# Main.net
KiCad netlist of a schematic drawn in Altium Designer
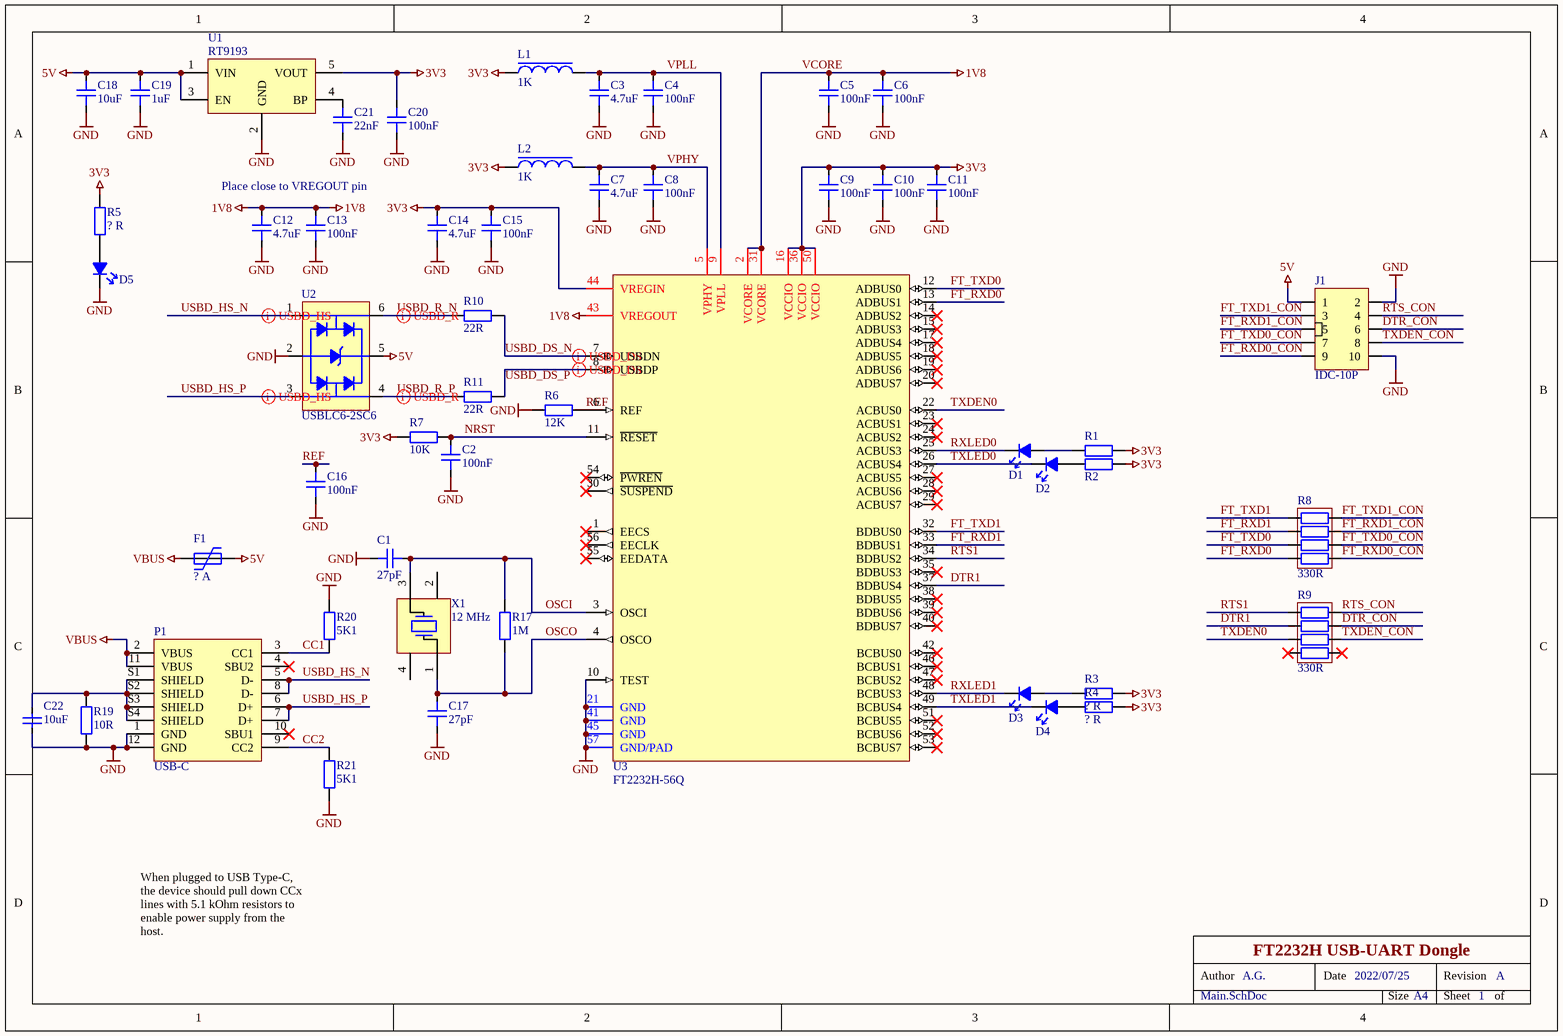
[diagram p0: Main.SchDoc]

(export (version "E")
  (design (tool "Eeschema 10.0.6"))
  (components
    (comp (ref "C1")
      (value "27pF")
      (footprint "0603C_RF_M")
      (description "Capacitor")
      (fields (field (name "TOLERANCE") "?") (field (name "MANUFACTURER") "Generic Brand"))
      (libsource (lib "AG.Generic") (part "C"))
    )
    (comp (ref "C2")
      (value "100nF")
      (footprint "0603C_RF_M")
      (description "Capacitor")
      (fields (field (name "TOLERANCE") "?") (field (name "MANUFACTURER") "Generic Brand"))
      (libsource (lib "AG.Generic") (part "C"))
    )
    (comp (ref "C3")
      (value "4.7uF")
      (footprint "0603C_RF_M")
      (description "Capacitor")
      (fields (field (name "TOLERANCE") "?") (field (name "MANUFACTURER") "Generic Brand"))
      (libsource (lib "AG.Generic") (part "C"))
    )
    (comp (ref "C4")
      (value "100nF")
      (footprint "0603C_RF_M")
      (description "Capacitor")
      (fields (field (name "TOLERANCE") "?") (field (name "MANUFACTURER") "Generic Brand"))
      (libsource (lib "AG.Generic") (part "C"))
    )
    (comp (ref "C5")
      (value "100nF")
      (footprint "0603C_RF_M")
      (description "Capacitor")
      (fields (field (name "TOLERANCE") "?") (field (name "MANUFACTURER") "Generic Brand"))
      (libsource (lib "AG.Generic") (part "C"))
    )
    (comp (ref "C6")
      (value "100nF")
      (footprint "0603C_RF_M")
      (description "Capacitor")
      (fields (field (name "TOLERANCE") "?") (field (name "MANUFACTURER") "Generic Brand"))
      (libsource (lib "AG.Generic") (part "C"))
    )
    (comp (ref "C7")
      (value "4.7uF")
      (footprint "0603C_RF_M")
      (description "Capacitor")
      (fields (field (name "TOLERANCE") "?") (field (name "MANUFACTURER") "Generic Brand"))
      (libsource (lib "AG.Generic") (part "C"))
    )
    (comp (ref "C8")
      (value "100nF")
      (footprint "0603C_RF_M")
      (description "Capacitor")
      (fields (field (name "TOLERANCE") "?") (field (name "MANUFACTURER") "Generic Brand"))
      (libsource (lib "AG.Generic") (part "C"))
    )
    (comp (ref "C9")
      (value "100nF")
      (footprint "0603C_RF_M")
      (description "Capacitor")
      (fields (field (name "TOLERANCE") "?") (field (name "MANUFACTURER") "Generic Brand"))
      (libsource (lib "AG.Generic") (part "C"))
    )
    (comp (ref "C10")
      (value "100nF")
      (footprint "0603C_RF_M")
      (description "Capacitor")
      (fields (field (name "TOLERANCE") "?") (field (name "MANUFACTURER") "Generic Brand"))
      (libsource (lib "AG.Generic") (part "C"))
    )
    (comp (ref "C11")
      (value "100nF")
      (footprint "0603C_RF_M")
      (description "Capacitor")
      (fields (field (name "TOLERANCE") "?") (field (name "MANUFACTURER") "Generic Brand"))
      (libsource (lib "AG.Generic") (part "C"))
    )
    (comp (ref "C12")
      (value "4.7uF")
      (footprint "0603C_RF_M")
      (description "Capacitor")
      (fields (field (name "TOLERANCE") "?") (field (name "MANUFACTURER") "Generic Brand"))
      (libsource (lib "AG.Generic") (part "C"))
    )
    (comp (ref "C13")
      (value "100nF")
      (footprint "0603C_RF_M")
      (description "Capacitor")
      (fields (field (name "TOLERANCE") "?") (field (name "MANUFACTURER") "Generic Brand"))
      (libsource (lib "AG.Generic") (part "C"))
    )
    (comp (ref "C14")
      (value "4.7uF")
      (footprint "0603C_RF_M")
      (description "Capacitor")
      (fields (field (name "TOLERANCE") "?") (field (name "MANUFACTURER") "Generic Brand"))
      (libsource (lib "AG.Generic") (part "C"))
    )
    (comp (ref "C15")
      (value "100nF")
      (footprint "0603C_RF_M")
      (description "Capacitor")
      (fields (field (name "TOLERANCE") "?") (field (name "MANUFACTURER") "Generic Brand"))
      (libsource (lib "AG.Generic") (part "C"))
    )
    (comp (ref "C16")
      (value "100nF")
      (footprint "0603C_RF_M")
      (description "Capacitor")
      (fields (field (name "TOLERANCE") "?") (field (name "MANUFACTURER") "Generic Brand"))
      (libsource (lib "AG.Generic") (part "C"))
    )
    (comp (ref "C17")
      (value "27pF")
      (footprint "0603C_RF_M")
      (description "Capacitor")
      (fields (field (name "TOLERANCE") "?") (field (name "MANUFACTURER") "Generic Brand"))
      (libsource (lib "AG.Generic") (part "C"))
    )
    (comp (ref "C18")
      (value "10uF")
      (footprint "0603C_RF_M")
      (description "Capacitor")
      (fields (field (name "TOLERANCE") "?") (field (name "MANUFACTURER") "Generic Brand"))
      (libsource (lib "AG.Generic") (part "C"))
    )
    (comp (ref "C19")
      (value "1uF")
      (footprint "0603C_RF_M")
      (description "Capacitor")
      (fields (field (name "TOLERANCE") "?") (field (name "MANUFACTURER") "Generic Brand"))
      (libsource (lib "AG.Generic") (part "C"))
    )
    (comp (ref "C20")
      (value "100nF")
      (footprint "0603C_RF_M")
      (description "Capacitor")
      (fields (field (name "TOLERANCE") "?") (field (name "MANUFACTURER") "Generic Brand"))
      (libsource (lib "AG.Generic") (part "C"))
    )
    (comp (ref "C21")
      (value "22nF")
      (footprint "0603C_RF_M")
      (description "Capacitor")
      (fields (field (name "TOLERANCE") "?") (field (name "MANUFACTURER") "Generic Brand"))
      (libsource (lib "AG.Generic") (part "C"))
    )
    (comp (ref "C22")
      (value "10uF")
      (footprint "0603C_RF_M")
      (description "Capacitor")
      (fields (field (name "TOLERANCE") "?") (field (name "MANUFACTURER") "Generic Brand"))
      (libsource (lib "") (part "C_1"))
    )
    (comp (ref "D1")
      (value "Unspecified")
      (footprint "0805LED_RF_M")
      (description "LED")
      (fields (field (name "MANUFACTURER") "Generic Brand"))
      (libsource (lib "AG.Generic") (part "LED"))
    )
    (comp (ref "D2")
      (value "Unspecified")
      (footprint "0805LED_RF_M")
      (description "LED")
      (fields (field (name "MANUFACTURER") "Generic Brand"))
      (libsource (lib "AG.Generic") (part "LED"))
    )
    (comp (ref "D3")
      (value "Unspecified")
      (footprint "0805LED_RF_M")
      (description "LED")
      (fields (field (name "MANUFACTURER") "Generic Brand"))
      (libsource (lib "AG.Generic") (part "LED"))
    )
    (comp (ref "D4")
      (value "Unspecified")
      (footprint "0805LED_RF_M")
      (description "LED")
      (fields (field (name "MANUFACTURER") "Generic Brand"))
      (libsource (lib "AG.Generic") (part "LED"))
    )
    (comp (ref "D5")
      (value "Unspecified")
      (footprint "0805LED_RF_M")
      (description "LED")
      (fields (field (name "MANUFACTURER") "Generic Brand"))
      (libsource (lib "AG.Generic") (part "LED"))
    )
    (comp (ref "F1")
      (value "? A")
      (footprint "AG.Passive:PTC_0805_RF_M")
      (description "Resettable Fuse")
      (fields (field (name "MANUFACTURER") "Generic Brand"))
      (libsource (lib "AG.Generic") (part "PPTC"))
    )
    (comp (ref "J1")
      (value "IDC-10P")
      (footprint "AG.Connectors:IDC-10_100MIL_SIDE")
      (description "IDC Connector Header Double Row 10 Position")
      (fields
        (field (name "MANUFACTURER") "Wurth Elektronik")
        (field (name "MANUFACTURER PART NO") "61201021621")
      )
      (libsource (lib "AG.Connectors") (part "IDC-10P"))
    )
    (comp (ref "L1")
      (value "1K")
      (footprint "AG.Chip:0603C_RF_M")
      (description "Ferrite Bead")
      (libsource (lib "AG.Generic") (part "FB"))
    )
    (comp (ref "L2")
      (value "1K")
      (footprint "AG.Chip:0603C_RF_M")
      (description "Ferrite Bead")
      (libsource (lib "AG.Generic") (part "FB"))
    )
    (comp (ref "P1")
      (value "USB-C")
      (footprint "AG.Connectors:USBC-16P-TH")
      (description "USB Type C Socket 16-Pin")
      (libsource (lib "AG.Connectors") (part "USBC-16P-TH"))
    )
    (comp (ref "R1")
      (value "? R")
      (footprint "0603R_RF_M")
      (description "Resistor")
      (fields (field (name "TOLERANCE") "?") (field (name "MANUFACTURER") "Generic Brand"))
      (libsource (lib "AG.Generic") (part "R"))
    )
    (comp (ref "R2")
      (value "? R")
      (footprint "0603R_RF_M")
      (description "Resistor")
      (fields (field (name "TOLERANCE") "?") (field (name "MANUFACTURER") "Generic Brand"))
      (libsource (lib "AG.Generic") (part "R"))
    )
    (comp (ref "R3")
      (value "? R")
      (footprint "0603R_RF_M")
      (description "Resistor")
      (fields (field (name "TOLERANCE") "?") (field (name "MANUFACTURER") "Generic Brand"))
      (libsource (lib "AG.Generic") (part "R"))
    )
    (comp (ref "R4")
      (value "? R")
      (footprint "0603R_RF_M")
      (description "Resistor")
      (fields (field (name "TOLERANCE") "?") (field (name "MANUFACTURER") "Generic Brand"))
      (libsource (lib "AG.Generic") (part "R"))
    )
    (comp (ref "R5")
      (value "? R")
      (footprint "0603R_RF_M")
      (description "Resistor")
      (fields (field (name "TOLERANCE") "?") (field (name "MANUFACTURER") "Generic Brand"))
      (libsource (lib "AG.Generic") (part "R"))
    )
    (comp (ref "R6")
      (value "12K")
      (footprint "0603R_RF_M")
      (description "Resistor")
      (fields (field (name "TOLERANCE") "?") (field (name "MANUFACTURER") "Generic Brand"))
      (libsource (lib "AG.Generic") (part "R"))
    )
    (comp (ref "R7")
      (value "10K")
      (footprint "0603R_RF_M")
      (description "Resistor")
      (fields (field (name "TOLERANCE") "?") (field (name "MANUFACTURER") "Generic Brand"))
      (libsource (lib "AG.Generic") (part "R"))
    )
    (comp (ref "R8")
      (value "330R")
      (footprint "Chip:R0603_ARR_4R_CNVX_RF_H")
      (description "Resistor Array 4x Isolated")
      (libsource (lib "AG.Generic") (part "RA-4"))
    )
    (comp (ref "R9")
      (value "330R")
      (footprint "Chip:R0603_ARR_4R_CNVX_RF_H")
      (description "Resistor Array 4x Isolated")
      (libsource (lib "AG.Generic") (part "RA-4"))
    )
    (comp (ref "R10")
      (value "22R")
      (footprint "Chip:R0402_RF_M")
      (description "Resistor")
      (fields (field (name "TOLERANCE") "?") (field (name "MANUFACTURER") "Generic Brand"))
      (libsource (lib "AG.Generic") (part "R"))
    )
    (comp (ref "R11")
      (value "22R")
      (footprint "Chip:R0402_RF_M")
      (description "Resistor")
      (fields (field (name "TOLERANCE") "?") (field (name "MANUFACTURER") "Generic Brand"))
      (libsource (lib "AG.Generic") (part "R"))
    )
    (comp (ref "R17")
      (value "1M")
      (footprint "0603R_RF_M")
      (description "Resistor")
      (fields (field (name "TOLERANCE") "?") (field (name "MANUFACTURER") "Generic Brand"))
      (libsource (lib "AG.Generic") (part "R"))
    )
    (comp (ref "R19")
      (value "10R")
      (footprint "0603R_RF_M")
      (description "Resistor")
      (fields (field (name "TOLERANCE") "?") (field (name "MANUFACTURER") "Generic Brand"))
      (libsource (lib "AG.Generic") (part "R"))
    )
    (comp (ref "R20")
      (value "5K1")
      (footprint "0603R_RF_M")
      (description "Resistor")
      (fields (field (name "TOLERANCE") "?") (field (name "MANUFACTURER") "Generic Brand"))
      (libsource (lib "AG.Generic") (part "R"))
    )
    (comp (ref "R21")
      (value "5K1")
      (footprint "0603R_RF_M")
      (description "Resistor")
      (fields (field (name "TOLERANCE") "?") (field (name "MANUFACTURER") "Generic Brand"))
      (libsource (lib "AG.Generic") (part "R"))
    )
    (comp (ref "U1")
      (value "RT9193")
      (footprint "AG.IC:TI_SOT-23-5")
      (description "IC REG LINEAR 300MA SOT23-5")
      (libsource (lib "AG.IC") (part "RT9193"))
    )
    (comp (ref "U2")
      (value "USBLC6-2SC6")
      (footprint "TI_SOT-23-6")
      (description "Low Capacitance USB ESD Protection")
      (fields (field (name "MANUFACTURER") "STMicroelectronics"))
      (libsource (lib "AG.Discrete") (part "USBLC6-2SC6"))
    )
    (comp (ref "U3")
      (value "FT2232H-56Q")
      (footprint "FTDI_VQFN-56_RF_M")
      (description "IC DUAL USB TO UART/FIFO 56VQFN")
      (fields (field (name "MANUFACTURER") "Future Technology Devices International Ltd"))
      (libsource (lib "AG.IC") (part "FT2232H-56Q"))
    )
    (comp (ref "X1")
      (value "12 MHz")
      (footprint "XTAL_3225")
      (description "Crystal Resonator (4 Leads)")
      (fields (field (name "MANUFACTURER") "Generic Brand") (field (name "TOLERANCE") "? ppm"))
      (libsource (lib "AG.Generic") (part "XT-4P"))
    )
  )
  (nets
    (net (code "1") (name "/CC1") (class "Default")
      (node (ref "P1") (pin "3") (pinfunction "CC1_3") (pintype "passive"))
      (node (ref "R20") (pin "2") (pintype "passive"))
    )
    (net (code "2") (name "/CC2") (class "Default")
      (node (ref "P1") (pin "9") (pinfunction "CC2_9") (pintype "passive"))
      (node (ref "R21") (pin "1") (pintype "passive"))
    )
    (net (code "3") (name "/DTR1") (class "Default")
      (node (ref "R9") (pin "2") (pintype "passive"))
      (node (ref "U3") (pin "37") (pinfunction "BDBUS4_37") (pintype "bidirectional"))
    )
    (net (code "4") (name "/DTR_CON") (class "Default")
      (node (ref "J1") (pin "6") (pinfunction "6_6") (pintype "passive"))
      (node (ref "R9") (pin "7") (pintype "passive"))
    )
    (net (code "5") (name "/FT_RXD0") (class "Default")
      (node (ref "R8") (pin "4") (pintype "passive"))
      (node (ref "U3") (pin "13") (pinfunction "ADBUS1_13") (pintype "bidirectional"))
    )
    (net (code "6") (name "/FT_RXD0_CON") (class "Default")
      (node (ref "J1") (pin "9") (pinfunction "9_9") (pintype "passive"))
      (node (ref "R8") (pin "5") (pintype "passive"))
    )
    (net (code "7") (name "/FT_RXD1") (class "Default")
      (node (ref "R8") (pin "2") (pintype "passive"))
      (node (ref "U3") (pin "33") (pinfunction "BDBUS1_33") (pintype "bidirectional"))
    )
    (net (code "8") (name "/FT_RXD1_CON") (class "Default")
      (node (ref "J1") (pin "5") (pinfunction "5_5") (pintype "passive"))
      (node (ref "R8") (pin "7") (pintype "passive"))
    )
    (net (code "9") (name "/FT_TXD0") (class "Default")
      (node (ref "R8") (pin "3") (pintype "passive"))
      (node (ref "U3") (pin "12") (pinfunction "ADBUS0_12") (pintype "bidirectional"))
    )
    (net (code "10") (name "/FT_TXD0_CON") (class "Default")
      (node (ref "J1") (pin "7") (pinfunction "7_7") (pintype "passive"))
      (node (ref "R8") (pin "6") (pintype "passive"))
    )
    (net (code "11") (name "/FT_TXD1") (class "Default")
      (node (ref "R8") (pin "1") (pintype "passive"))
      (node (ref "U3") (pin "32") (pinfunction "BDBUS0_32") (pintype "bidirectional"))
    )
    (net (code "12") (name "/FT_TXD1_CON") (class "Default")
      (node (ref "J1") (pin "3") (pinfunction "3_3") (pintype "passive"))
      (node (ref "R8") (pin "8") (pintype "passive"))
    )
    (net (code "13") (name "/NRST") (class "Default")
      (node (ref "C2") (pin "1") (pinfunction "1_1") (pintype "passive"))
      (node (ref "R7") (pin "2") (pintype "passive"))
      (node (ref "U3") (pin "11") (pinfunction "~{RESET}_11") (pintype "input"))
    )
    (net (code "14") (name "/OSCI") (class "Default")
      (node (ref "C1") (pin "2") (pinfunction "2_2") (pintype "passive"))
      (node (ref "R17") (pin "1") (pintype "passive"))
      (node (ref "U3") (pin "3") (pinfunction "OSCI_3") (pintype "input"))
      (node (ref "X1") (pin "3") (pinfunction "X2_3") (pintype "passive"))
    )
    (net (code "15") (name "/OSCO") (class "Default")
      (node (ref "C17") (pin "2") (pinfunction "2_2") (pintype "passive"))
      (node (ref "R17") (pin "2") (pintype "passive"))
      (node (ref "U3") (pin "4") (pinfunction "OSCO_4") (pintype "output"))
      (node (ref "X1") (pin "1") (pinfunction "X1_1") (pintype "passive"))
    )
    (net (code "16") (name "/REF") (class "Default")
      (node (ref "C16") (pin "1") (pinfunction "1_1") (pintype "passive"))
      (node (ref "R6") (pin "2") (pintype "passive"))
      (node (ref "U3") (pin "6") (pinfunction "REF_6") (pintype "input"))
    )
    (net (code "17") (name "/RTS1") (class "Default")
      (node (ref "R9") (pin "1") (pintype "passive"))
      (node (ref "U3") (pin "34") (pinfunction "BDBUS2_34") (pintype "bidirectional"))
    )
    (net (code "18") (name "/RTS_CON") (class "Default")
      (node (ref "J1") (pin "4") (pinfunction "4_4") (pintype "passive"))
      (node (ref "R9") (pin "8") (pintype "passive"))
    )
    (net (code "19") (name "/RXLED0") (class "Default")
      (node (ref "D1") (pin "C") (pinfunction "C_C") (pintype "passive"))
      (node (ref "U3") (pin "25") (pinfunction "ACBUS3_25") (pintype "bidirectional"))
    )
    (net (code "20") (name "/RXLED1") (class "Default")
      (node (ref "D3") (pin "C") (pinfunction "C_C") (pintype "passive"))
      (node (ref "U3") (pin "48") (pinfunction "BCBUS3_48") (pintype "bidirectional"))
    )
    (net (code "21") (name "/TXDEN0") (class "Default")
      (node (ref "R9") (pin "3") (pintype "passive"))
      (node (ref "U3") (pin "22") (pinfunction "ACBUS0_22") (pintype "bidirectional"))
    )
    (net (code "22") (name "/TXDEN_CON") (class "Default")
      (node (ref "J1") (pin "8") (pinfunction "8_8") (pintype "passive"))
      (node (ref "R9") (pin "6") (pintype "passive"))
    )
    (net (code "23") (name "/TXLED0") (class "Default")
      (node (ref "D2") (pin "C") (pinfunction "C_C") (pintype "passive"))
      (node (ref "U3") (pin "26") (pinfunction "ACBUS4_26") (pintype "bidirectional"))
    )
    (net (code "24") (name "/TXLED1") (class "Default")
      (node (ref "D4") (pin "C") (pinfunction "C_C") (pintype "passive"))
      (node (ref "U3") (pin "49") (pinfunction "BCBUS4_49") (pintype "bidirectional"))
    )
    (net (code "25") (name "/USBD_DS_N") (class "Default")
      (node (ref "R10") (pin "2") (pintype "passive"))
      (node (ref "U3") (pin "7") (pinfunction "USBDN_7") (pintype "bidirectional"))
    )
    (net (code "26") (name "/USBD_DS_P") (class "Default")
      (node (ref "R11") (pin "2") (pintype "passive"))
      (node (ref "U3") (pin "8") (pinfunction "USBDP_8") (pintype "bidirectional"))
    )
    (net (code "27") (name "/USBD_HS_N") (class "Default")
      (node (ref "P1") (pin "5") (pinfunction "D-_5") (pintype "passive"))
      (node (ref "P1") (pin "8") (pinfunction "D-_8") (pintype "passive"))
      (node (ref "U2") (pin "1") (pinfunction "1_1") (pintype "passive"))
    )
    (net (code "28") (name "/USBD_HS_P") (class "Default")
      (node (ref "P1") (pin "6") (pinfunction "D+_6") (pintype "passive"))
      (node (ref "P1") (pin "7") (pinfunction "D+_7") (pintype "passive"))
      (node (ref "U2") (pin "3") (pinfunction "3_3") (pintype "passive"))
    )
    (net (code "29") (name "/USBD_R_N") (class "Default")
      (node (ref "R10") (pin "1") (pintype "passive"))
      (node (ref "U2") (pin "6") (pinfunction "6_6") (pintype "passive"))
    )
    (net (code "30") (name "/USBD_R_P") (class "Default")
      (node (ref "R11") (pin "1") (pintype "passive"))
      (node (ref "U2") (pin "4") (pinfunction "4_4") (pintype "passive"))
    )
    (net (code "31") (name "/VPHY") (class "Default")
      (node (ref "C7") (pin "2") (pinfunction "2_2") (pintype "passive"))
      (node (ref "C8") (pin "2") (pinfunction "2_2") (pintype "passive"))
      (node (ref "L2") (pin "2") (pinfunction "2_2") (pintype "passive"))
      (node (ref "U3") (pin "5") (pinfunction "VPHY_5") (pintype "power_in"))
    )
    (net (code "32") (name "/VPLL") (class "Default")
      (node (ref "C3") (pin "2") (pinfunction "2_2") (pintype "passive"))
      (node (ref "C4") (pin "2") (pinfunction "2_2") (pintype "passive"))
      (node (ref "L1") (pin "2") (pinfunction "2_2") (pintype "passive"))
      (node (ref "U3") (pin "9") (pinfunction "VPLL_9") (pintype "power_in"))
    )
    (net (code "33") (name "1V8") (class "Default")
      (node (ref "C12") (pin "2") (pinfunction "2_2") (pintype "passive"))
      (node (ref "C13") (pin "2") (pinfunction "2_2") (pintype "passive"))
      (node (ref "C5") (pin "2") (pinfunction "2_2") (pintype "passive"))
      (node (ref "C6") (pin "2") (pinfunction "2_2") (pintype "passive"))
      (node (ref "U3") (pin "2") (pinfunction "VCORE_2") (pintype "power_in"))
      (node (ref "U3") (pin "31") (pinfunction "VCORE_31") (pintype "power_in"))
      (node (ref "U3") (pin "43") (pinfunction "VREGOUT_43") (pintype "power_in"))
    )
    (net (code "34") (name "3V3") (class "Default")
      (node (ref "C10") (pin "2") (pinfunction "2_2") (pintype "passive"))
      (node (ref "C11") (pin "2") (pinfunction "2_2") (pintype "passive"))
      (node (ref "C14") (pin "2") (pinfunction "2_2") (pintype "passive"))
      (node (ref "C15") (pin "2") (pinfunction "2_2") (pintype "passive"))
      (node (ref "C20") (pin "2") (pinfunction "2_2") (pintype "passive"))
      (node (ref "C9") (pin "2") (pinfunction "2_2") (pintype "passive"))
      (node (ref "L1") (pin "1") (pinfunction "1_1") (pintype "passive"))
      (node (ref "L2") (pin "1") (pinfunction "1_1") (pintype "passive"))
      (node (ref "R1") (pin "1") (pintype "passive"))
      (node (ref "R2") (pin "1") (pintype "passive"))
      (node (ref "R3") (pin "1") (pintype "passive"))
      (node (ref "R4") (pin "1") (pintype "passive"))
      (node (ref "R5") (pin "1") (pintype "passive"))
      (node (ref "R7") (pin "1") (pintype "passive"))
      (node (ref "U1") (pin "5") (pinfunction "VOUT_5") (pintype "passive"))
      (node (ref "U3") (pin "16") (pinfunction "VCCIO_16") (pintype "power_in"))
      (node (ref "U3") (pin "36") (pinfunction "VCCIO_36") (pintype "power_in"))
      (node (ref "U3") (pin "44") (pinfunction "VREGIN_44") (pintype "power_in"))
      (node (ref "U3") (pin "50") (pinfunction "VCCIO_50") (pintype "power_in"))
    )
    (net (code "35") (name "5V") (class "Default")
      (node (ref "C18") (pin "1") (pinfunction "1_1") (pintype "passive"))
      (node (ref "C19") (pin "1") (pinfunction "1_1") (pintype "passive"))
      (node (ref "F1") (pin "2") (pinfunction "2_2") (pintype "passive"))
      (node (ref "J1") (pin "1") (pinfunction "1_1") (pintype "passive"))
      (node (ref "U1") (pin "1") (pinfunction "VIN_1") (pintype "passive"))
      (node (ref "U1") (pin "3") (pinfunction "EN_3") (pintype "passive"))
      (node (ref "U2") (pin "5") (pinfunction "5_5") (pintype "passive"))
    )
    (net (code "36") (name "GND") (class "Default")
      (node (ref "C1") (pin "1") (pinfunction "1_1") (pintype "passive"))
      (node (ref "C10") (pin "1") (pinfunction "1_1") (pintype "passive"))
      (node (ref "C11") (pin "1") (pinfunction "1_1") (pintype "passive"))
      (node (ref "C12") (pin "1") (pinfunction "1_1") (pintype "passive"))
      (node (ref "C13") (pin "1") (pinfunction "1_1") (pintype "passive"))
      (node (ref "C14") (pin "1") (pinfunction "1_1") (pintype "passive"))
      (node (ref "C15") (pin "1") (pinfunction "1_1") (pintype "passive"))
      (node (ref "C16") (pin "2") (pinfunction "2_2") (pintype "passive"))
      (node (ref "C17") (pin "1") (pinfunction "1_1") (pintype "passive"))
      (node (ref "C18") (pin "2") (pinfunction "2_2") (pintype "passive"))
      (node (ref "C19") (pin "2") (pinfunction "2_2") (pintype "passive"))
      (node (ref "C2") (pin "2") (pinfunction "2_2") (pintype "passive"))
      (node (ref "C20") (pin "1") (pinfunction "1_1") (pintype "passive"))
      (node (ref "C21") (pin "1") (pinfunction "1_1") (pintype "passive"))
      (node (ref "C22") (pin "1") (pinfunction "1_1") (pintype "passive"))
      (node (ref "C3") (pin "1") (pinfunction "1_1") (pintype "passive"))
      (node (ref "C4") (pin "1") (pinfunction "1_1") (pintype "passive"))
      (node (ref "C5") (pin "1") (pinfunction "1_1") (pintype "passive"))
      (node (ref "C6") (pin "1") (pinfunction "1_1") (pintype "passive"))
      (node (ref "C7") (pin "1") (pinfunction "1_1") (pintype "passive"))
      (node (ref "C8") (pin "1") (pinfunction "1_1") (pintype "passive"))
      (node (ref "C9") (pin "1") (pinfunction "1_1") (pintype "passive"))
      (node (ref "D5") (pin "C") (pinfunction "C_C") (pintype "passive"))
      (node (ref "J1") (pin "10") (pinfunction "10_10") (pintype "passive"))
      (node (ref "J1") (pin "2") (pinfunction "2_2") (pintype "passive"))
      (node (ref "P1") (pin "1") (pinfunction "GND_1") (pintype "power_in"))
      (node (ref "P1") (pin "12") (pinfunction "GND_12") (pintype "power_in"))
      (node (ref "R19") (pin "2") (pintype "passive"))
      (node (ref "R20") (pin "1") (pintype "passive"))
      (node (ref "R21") (pin "2") (pintype "passive"))
      (node (ref "R6") (pin "1") (pintype "passive"))
      (node (ref "U1") (pin "2") (pinfunction "GND_2") (pintype "passive"))
      (node (ref "U2") (pin "2") (pinfunction "2_2") (pintype "passive"))
      (node (ref "U3") (pin "10") (pinfunction "TEST_10") (pintype "input"))
      (node (ref "U3") (pin "21") (pinfunction "GND_21") (pintype "power_in"))
      (node (ref "U3") (pin "41") (pinfunction "GND_41") (pintype "power_in"))
      (node (ref "U3") (pin "45") (pinfunction "GND_45") (pintype "power_in"))
      (node (ref "U3") (pin "57") (pinfunction "GND/PAD_57") (pintype "power_in"))
    )
    (net (code "37") (name "Net-(C22-Pad2)") (class "Default")
      (node (ref "C22") (pin "2") (pinfunction "2_2") (pintype "passive"))
      (node (ref "P1") (pin "S1") (pinfunction "SHIELD_S1") (pintype "passive"))
      (node (ref "P1") (pin "S2") (pinfunction "SHIELD_S2") (pintype "passive"))
      (node (ref "P1") (pin "S3") (pinfunction "SHIELD_S3") (pintype "passive"))
      (node (ref "P1") (pin "S4") (pinfunction "SHIELD_S4") (pintype "passive"))
      (node (ref "R19") (pin "1") (pintype "passive"))
    )
    (net (code "38") (name "Net-(D1-PadA)") (class "Default")
      (node (ref "D1") (pin "A") (pinfunction "A_A") (pintype "passive"))
      (node (ref "R1") (pin "2") (pintype "passive"))
    )
    (net (code "39") (name "Net-(D2-PadA)") (class "Default")
      (node (ref "D2") (pin "A") (pinfunction "A_A") (pintype "passive"))
      (node (ref "R2") (pin "2") (pintype "passive"))
    )
    (net (code "40") (name "Net-(D3-PadA)") (class "Default")
      (node (ref "D3") (pin "A") (pinfunction "A_A") (pintype "passive"))
      (node (ref "R3") (pin "2") (pintype "passive"))
    )
    (net (code "41") (name "Net-(D4-PadA)") (class "Default")
      (node (ref "D4") (pin "A") (pinfunction "A_A") (pintype "passive"))
      (node (ref "R4") (pin "2") (pintype "passive"))
    )
    (net (code "42") (name "Net-(D5-PadA)") (class "Default")
      (node (ref "D5") (pin "A") (pinfunction "A_A") (pintype "passive"))
      (node (ref "R5") (pin "2") (pintype "passive"))
    )
    (net (code "43") (name "Net-(U1-BP)") (class "Default")
      (node (ref "C21") (pin "2") (pinfunction "2_2") (pintype "passive"))
      (node (ref "U1") (pin "4") (pinfunction "BP_4") (pintype "passive"))
    )
    (net (code "44") (name "VBUS") (class "Default")
      (node (ref "F1") (pin "1") (pinfunction "1_1") (pintype "passive"))
      (node (ref "P1") (pin "11") (pinfunction "VBUS_11") (pintype "power_in"))
      (node (ref "P1") (pin "2") (pinfunction "VBUS_2") (pintype "power_in"))
    )
    (net (code "45") (name "unconnected-(P1-SBU1-Pad10)") (class "Default")
      (node (ref "P1") (pin "10") (pinfunction "SBU1_10") (pintype "passive+no_connect"))
    )
    (net (code "46") (name "unconnected-(P1-SBU2-Pad4)") (class "Default")
      (node (ref "P1") (pin "4") (pinfunction "SBU2_4") (pintype "passive+no_connect"))
    )
    (net (code "47") (name "unconnected-(R9-Pad4)") (class "Default")
      (node (ref "R9") (pin "4") (pintype "passive+no_connect"))
    )
    (net (code "48") (name "unconnected-(R9-Pad5)") (class "Default")
      (node (ref "R9") (pin "5") (pintype "passive+no_connect"))
    )
    (net (code "49") (name "unconnected-(U3-ACBUS1-Pad23)") (class "Default")
      (node (ref "U3") (pin "23") (pinfunction "ACBUS1_23") (pintype "bidirectional+no_connect"))
    )
    (net (code "50") (name "unconnected-(U3-ACBUS2-Pad24)") (class "Default")
      (node (ref "U3") (pin "24") (pinfunction "ACBUS2_24") (pintype "bidirectional+no_connect"))
    )
    (net (code "51") (name "unconnected-(U3-ACBUS5-Pad27)") (class "Default")
      (node (ref "U3") (pin "27") (pinfunction "ACBUS5_27") (pintype "bidirectional+no_connect"))
    )
    (net (code "52") (name "unconnected-(U3-ACBUS6-Pad28)") (class "Default")
      (node (ref "U3") (pin "28") (pinfunction "ACBUS6_28") (pintype "bidirectional+no_connect"))
    )
    (net (code "53") (name "unconnected-(U3-ACBUS7-Pad29)") (class "Default")
      (node (ref "U3") (pin "29") (pinfunction "ACBUS7_29") (pintype "bidirectional+no_connect"))
    )
    (net (code "54") (name "unconnected-(U3-ADBUS2-Pad14)") (class "Default")
      (node (ref "U3") (pin "14") (pinfunction "ADBUS2_14") (pintype "bidirectional+no_connect"))
    )
    (net (code "55") (name "unconnected-(U3-ADBUS3-Pad15)") (class "Default")
      (node (ref "U3") (pin "15") (pinfunction "ADBUS3_15") (pintype "bidirectional+no_connect"))
    )
    (net (code "56") (name "unconnected-(U3-ADBUS4-Pad17)") (class "Default")
      (node (ref "U3") (pin "17") (pinfunction "ADBUS4_17") (pintype "bidirectional+no_connect"))
    )
    (net (code "57") (name "unconnected-(U3-ADBUS5-Pad18)") (class "Default")
      (node (ref "U3") (pin "18") (pinfunction "ADBUS5_18") (pintype "bidirectional+no_connect"))
    )
    (net (code "58") (name "unconnected-(U3-ADBUS6-Pad19)") (class "Default")
      (node (ref "U3") (pin "19") (pinfunction "ADBUS6_19") (pintype "bidirectional+no_connect"))
    )
    (net (code "59") (name "unconnected-(U3-ADBUS7-Pad20)") (class "Default")
      (node (ref "U3") (pin "20") (pinfunction "ADBUS7_20") (pintype "bidirectional+no_connect"))
    )
    (net (code "60") (name "unconnected-(U3-BCBUS0-Pad42)") (class "Default")
      (node (ref "U3") (pin "42") (pinfunction "BCBUS0_42") (pintype "bidirectional+no_connect"))
    )
    (net (code "61") (name "unconnected-(U3-BCBUS1-Pad46)") (class "Default")
      (node (ref "U3") (pin "46") (pinfunction "BCBUS1_46") (pintype "bidirectional+no_connect"))
    )
    (net (code "62") (name "unconnected-(U3-BCBUS2-Pad47)") (class "Default")
      (node (ref "U3") (pin "47") (pinfunction "BCBUS2_47") (pintype "bidirectional+no_connect"))
    )
    (net (code "63") (name "unconnected-(U3-BCBUS5-Pad51)") (class "Default")
      (node (ref "U3") (pin "51") (pinfunction "BCBUS5_51") (pintype "bidirectional+no_connect"))
    )
    (net (code "64") (name "unconnected-(U3-BCBUS6-Pad52)") (class "Default")
      (node (ref "U3") (pin "52") (pinfunction "BCBUS6_52") (pintype "bidirectional+no_connect"))
    )
    (net (code "65") (name "unconnected-(U3-BCBUS7-Pad53)") (class "Default")
      (node (ref "U3") (pin "53") (pinfunction "BCBUS7_53") (pintype "bidirectional+no_connect"))
    )
    (net (code "66") (name "unconnected-(U3-BDBUS3-Pad35)") (class "Default")
      (node (ref "U3") (pin "35") (pinfunction "BDBUS3_35") (pintype "bidirectional+no_connect"))
    )
    (net (code "67") (name "unconnected-(U3-BDBUS5-Pad38)") (class "Default")
      (node (ref "U3") (pin "38") (pinfunction "BDBUS5_38") (pintype "bidirectional+no_connect"))
    )
    (net (code "68") (name "unconnected-(U3-BDBUS6-Pad39)") (class "Default")
      (node (ref "U3") (pin "39") (pinfunction "BDBUS6_39") (pintype "bidirectional+no_connect"))
    )
    (net (code "69") (name "unconnected-(U3-BDBUS7-Pad40)") (class "Default")
      (node (ref "U3") (pin "40") (pinfunction "BDBUS7_40") (pintype "bidirectional+no_connect"))
    )
    (net (code "70") (name "unconnected-(U3-EECLK-Pad56)") (class "Default")
      (node (ref "U3") (pin "56") (pinfunction "EECLK_56") (pintype "output+no_connect"))
    )
    (net (code "71") (name "unconnected-(U3-EECS-Pad1)") (class "Default")
      (node (ref "U3") (pin "1") (pinfunction "EECS_1") (pintype "output+no_connect"))
    )
    (net (code "72") (name "unconnected-(U3-EEDATA-Pad55)") (class "Default")
      (node (ref "U3") (pin "55") (pinfunction "EEDATA_55") (pintype "bidirectional+no_connect"))
    )
    (net (code "73") (name "unconnected-(U3-~{PWREN}-Pad54)") (class "Default")
      (node (ref "U3") (pin "54") (pinfunction "~{PWREN}_54") (pintype "bidirectional+no_connect"))
    )
    (net (code "74") (name "unconnected-(U3-~{SUSPEND}-Pad30)") (class "Default")
      (node (ref "U3") (pin "30") (pinfunction "~{SUSPEND}_30") (pintype "output+no_connect"))
    )
    (net (code "75") (name "unconnected-(X1-GND-Pad2)") (class "Default")
      (node (ref "X1") (pin "2") (pinfunction "GND_2") (pintype "passive"))
    )
    (net (code "76") (name "unconnected-(X1-GND-Pad4)") (class "Default")
      (node (ref "X1") (pin "4") (pinfunction "GND_4") (pintype "passive"))
    )
  )
)
